# Unicorn_Light_Meter.net
KiCad netlist of a schematic drawn in EAGLE
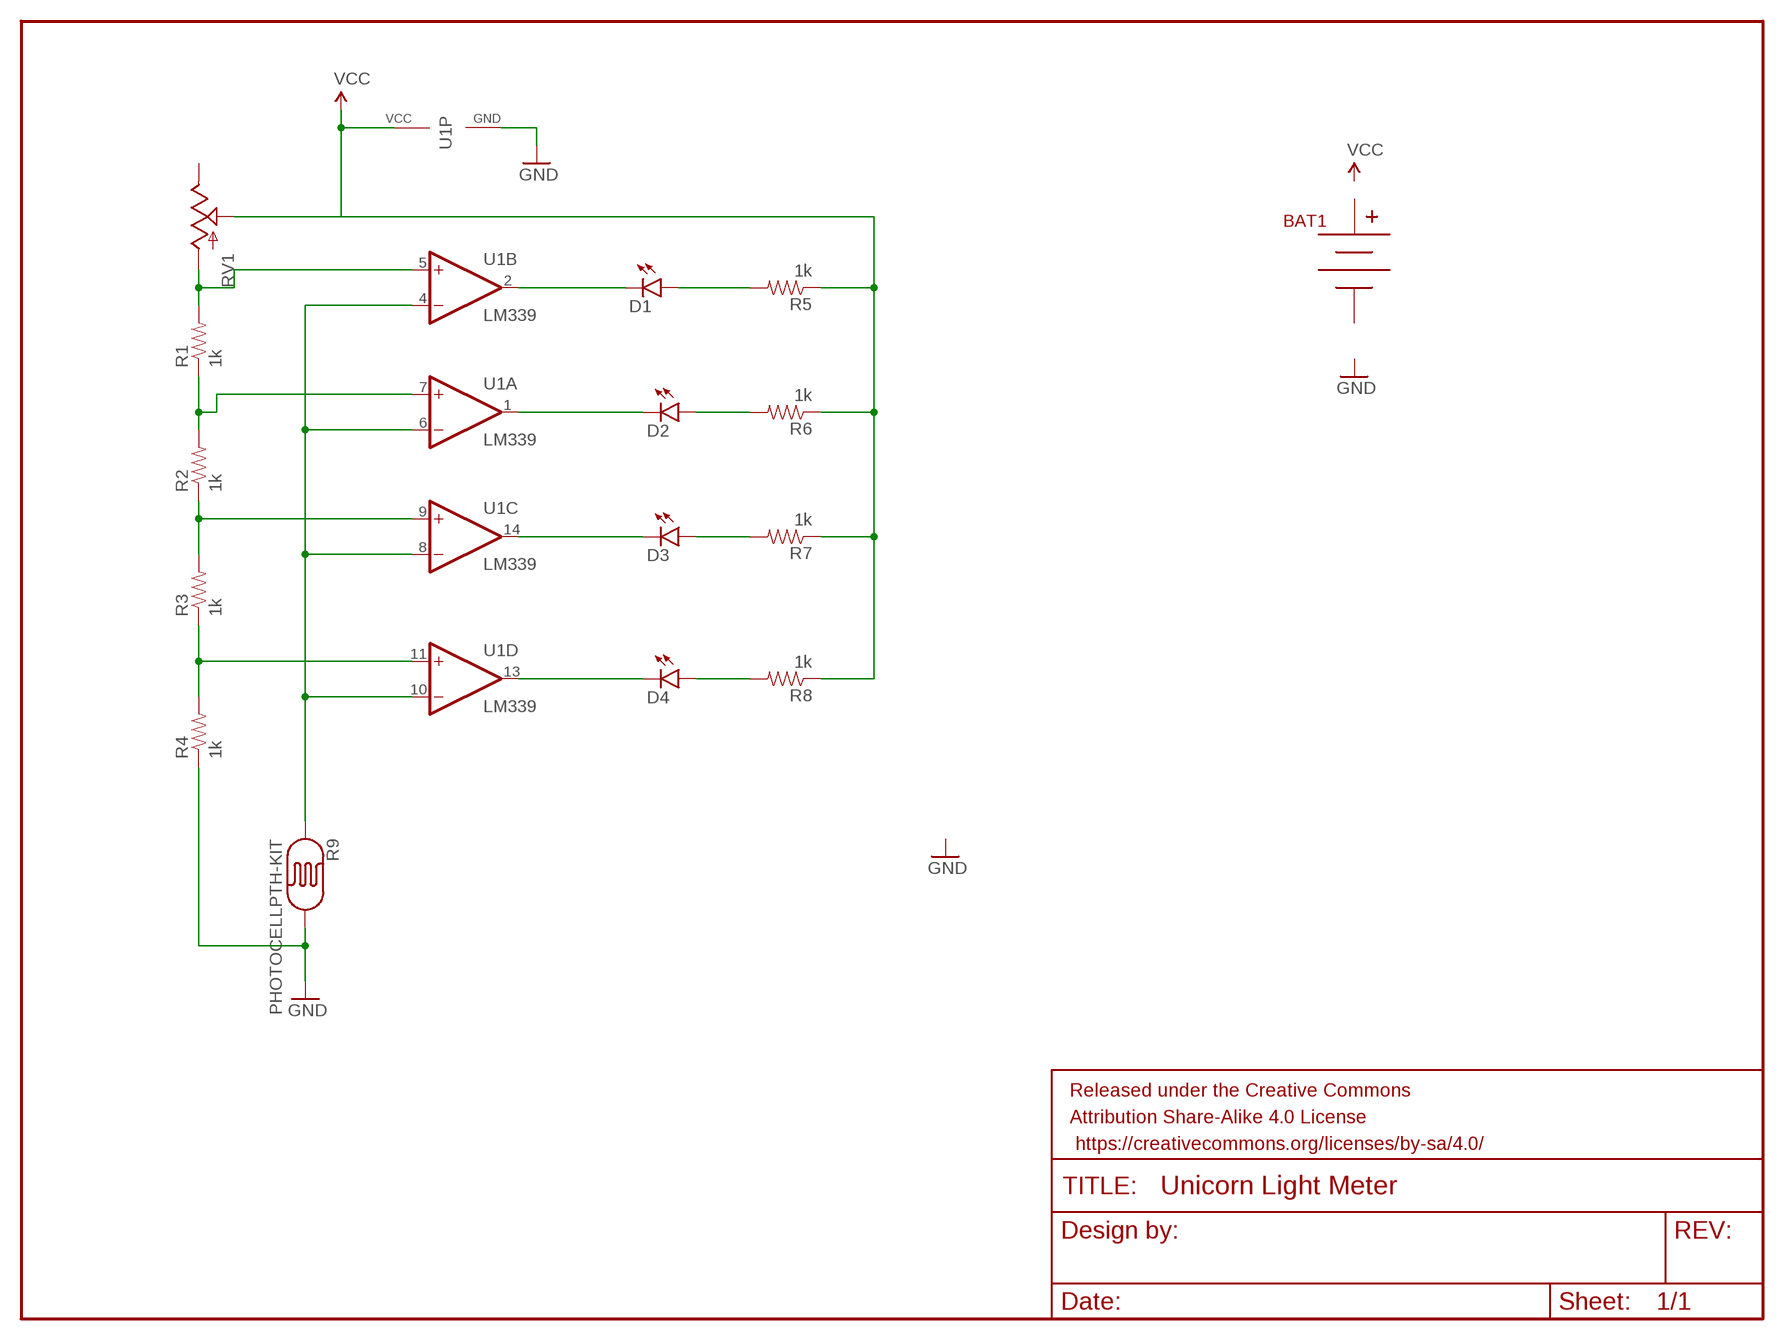
[diagram p0: schematic, sheet 1]

(export (version "E")
  (design (tool "Eeschema 10.0.6"))
  (components
    (comp (ref "BAT1")
      (value "BC9VPCKIT_SOLDERMASK")
      (footprint "eagle-import:BC9VPC_KIT")
      (libsource (lib "eagle-import") (part "BC9VPCKIT_SOLDERMASK"))
    )
    (comp (ref "D1")
      (value "LED5MM")
      (footprint "eagle-import:LED5MM")
      (libsource (lib "eagle-import") (part "LED5MM"))
    )
    (comp (ref "D2")
      (value "LED5MM")
      (footprint "eagle-import:LED5MM")
      (libsource (lib "eagle-import") (part "LED5MM"))
    )
    (comp (ref "D3")
      (value "LED5MM")
      (footprint "eagle-import:LED5MM")
      (libsource (lib "eagle-import") (part "LED5MM"))
    )
    (comp (ref "D4")
      (value "LED5MM")
      (footprint "eagle-import:LED5MM")
      (libsource (lib "eagle-import") (part "LED5MM"))
    )
    (comp (ref "FRAME1")
      (value "FRAME-LETTER")
      (footprint "eagle-import:CREATIVE_COMMONS")
      (libsource (lib "eagle-import") (part "FRAME-LETTER"))
    )
    (comp (ref "R1")
      (value "1k")
      (footprint "eagle-import:AXIAL-0.3EZ")
      (libsource (lib "eagle-import") (part "1KOHM-1/4W-5%(PTH)HORIZ-KIT"))
    )
    (comp (ref "R2")
      (value "1k")
      (footprint "eagle-import:AXIAL-0.3EZ")
      (libsource (lib "eagle-import") (part "1KOHM-1/4W-5%(PTH)HORIZ-KIT"))
    )
    (comp (ref "R3")
      (value "1k")
      (footprint "eagle-import:AXIAL-0.3EZ")
      (libsource (lib "eagle-import") (part "1KOHM-1/4W-5%(PTH)HORIZ-KIT"))
    )
    (comp (ref "R4")
      (value "1k")
      (footprint "eagle-import:AXIAL-0.3EZ")
      (libsource (lib "eagle-import") (part "1KOHM-1/4W-5%(PTH)HORIZ-KIT"))
    )
    (comp (ref "R5")
      (value "1k")
      (footprint "eagle-import:AXIAL-0.3EZ")
      (libsource (lib "eagle-import") (part "1KOHM-1/4W-5%(PTH)HORIZ-KIT"))
    )
    (comp (ref "R6")
      (value "1k")
      (footprint "eagle-import:AXIAL-0.3EZ")
      (libsource (lib "eagle-import") (part "1KOHM-1/4W-5%(PTH)HORIZ-KIT"))
    )
    (comp (ref "R7")
      (value "1k")
      (footprint "eagle-import:AXIAL-0.3EZ")
      (libsource (lib "eagle-import") (part "1KOHM-1/4W-5%(PTH)HORIZ-KIT"))
    )
    (comp (ref "R8")
      (value "1k")
      (footprint "eagle-import:AXIAL-0.3EZ")
      (libsource (lib "eagle-import") (part "1KOHM-1/4W-5%(PTH)HORIZ-KIT"))
    )
    (comp (ref "R9")
      (value "PHOTOCELLPTH-KIT")
      (footprint "eagle-import:PHOTOCELL-KIT")
      (libsource (lib "eagle-import") (part "PHOTOCELLPTH-KIT"))
    )
    (comp (ref "RV1")
      (value "POT100K_3362U")
      (footprint "eagle-import:3362U")
      (libsource (lib "eagle-import") (part "POT100K_3362U"))
    )
    (comp (ref "U1")
      (value "LM339")
      (footprint "eagle-import:TSSOP-14")
      (fields (field (name "PARTNUM") "LM339PWR"))
      (libsource (lib "eagle-import") (part "LM339"))
    )
  )
  (nets
    (net (code "1") (name "GND") (class "Default")
      (node (ref "R4") (pin "P$1") (pinfunction "1_P$1") (pintype "passive"))
      (node (ref "R9") (pin "2") (pinfunction "P$2_2") (pintype "bidirectional"))
      (node (ref "U1") (pin "12") (pinfunction "GND_12") (pintype "power_in"))
    )
    (net (code "2") (name "Net-(D1-C)") (class "Default")
      (node (ref "D1") (pin "K") (pinfunction "C_K") (pintype "passive"))
      (node (ref "U1") (pin "2") (pinfunction "OUT_2") (pintype "output"))
    )
    (net (code "3") (name "Net-(D2-C)") (class "Default")
      (node (ref "D2") (pin "K") (pinfunction "C_K") (pintype "passive"))
      (node (ref "U1") (pin "1") (pinfunction "OUT_1") (pintype "output"))
    )
    (net (code "4") (name "Net-(D3-C)") (class "Default")
      (node (ref "D3") (pin "K") (pinfunction "C_K") (pintype "passive"))
      (node (ref "U1") (pin "14") (pinfunction "OUT_14") (pintype "output"))
    )
    (net (code "5") (name "Net-(D4-C)") (class "Default")
      (node (ref "D4") (pin "K") (pinfunction "C_K") (pintype "passive"))
      (node (ref "U1") (pin "13") (pinfunction "OUT_13") (pintype "output"))
    )
    (net (code "6") (name "Net-(R1-1)") (class "Default")
      (node (ref "R1") (pin "P$1") (pinfunction "1_P$1") (pintype "passive"))
      (node (ref "R2") (pin "P$2") (pinfunction "2_P$2") (pintype "passive"))
      (node (ref "U1") (pin "7") (pinfunction "+IN_7") (pintype "input"))
    )
    (net (code "7") (name "Net-(R1-2)") (class "Default")
      (node (ref "R1") (pin "P$2") (pinfunction "2_P$2") (pintype "passive"))
      (node (ref "RV1") (pin "P$3") (pinfunction "A_P$3") (pintype "passive"))
      (node (ref "U1") (pin "5") (pinfunction "+IN_5") (pintype "input"))
    )
    (net (code "8") (name "Net-(R2-1)") (class "Default")
      (node (ref "R2") (pin "P$1") (pinfunction "1_P$1") (pintype "passive"))
      (node (ref "R3") (pin "P$2") (pinfunction "2_P$2") (pintype "passive"))
      (node (ref "U1") (pin "9") (pinfunction "+IN_9") (pintype "input"))
    )
    (net (code "9") (name "Net-(R3-1)") (class "Default")
      (node (ref "R3") (pin "P$1") (pinfunction "1_P$1") (pintype "passive"))
      (node (ref "R4") (pin "P$2") (pinfunction "2_P$2") (pintype "passive"))
      (node (ref "U1") (pin "11") (pinfunction "+IN_11") (pintype "input"))
    )
    (net (code "10") (name "Net-(R5-2)") (class "Default")
      (node (ref "D1") (pin "A") (pinfunction "A_A") (pintype "passive"))
      (node (ref "R5") (pin "P$2") (pinfunction "2_P$2") (pintype "passive"))
    )
    (net (code "11") (name "Net-(R6-2)") (class "Default")
      (node (ref "D2") (pin "A") (pinfunction "A_A") (pintype "passive"))
      (node (ref "R6") (pin "P$2") (pinfunction "2_P$2") (pintype "passive"))
    )
    (net (code "12") (name "Net-(R7-2)") (class "Default")
      (node (ref "D3") (pin "A") (pinfunction "A_A") (pintype "passive"))
      (node (ref "R7") (pin "P$2") (pinfunction "2_P$2") (pintype "passive"))
    )
    (net (code "13") (name "Net-(R8-2)") (class "Default")
      (node (ref "D4") (pin "A") (pinfunction "A_A") (pintype "passive"))
      (node (ref "R8") (pin "P$2") (pinfunction "2_P$2") (pintype "passive"))
    )
    (net (code "14") (name "Net-(R9-P$1)") (class "Default")
      (node (ref "R9") (pin "1") (pinfunction "P$1_1") (pintype "bidirectional"))
      (node (ref "U1") (pin "10") (pinfunction "-IN_10") (pintype "input"))
      (node (ref "U1") (pin "4") (pinfunction "-IN_4") (pintype "input"))
      (node (ref "U1") (pin "6") (pinfunction "-IN_6") (pintype "input"))
      (node (ref "U1") (pin "8") (pinfunction "-IN_8") (pintype "input"))
    )
    (net (code "15") (name "VCC") (class "Default")
      (node (ref "R5") (pin "P$1") (pinfunction "1_P$1") (pintype "passive"))
      (node (ref "R6") (pin "P$1") (pinfunction "1_P$1") (pintype "passive"))
      (node (ref "R7") (pin "P$1") (pinfunction "1_P$1") (pintype "passive"))
      (node (ref "R8") (pin "P$1") (pinfunction "1_P$1") (pintype "passive"))
      (node (ref "RV1") (pin "P$2") (pinfunction "S_P$2") (pintype "passive"))
      (node (ref "U1") (pin "3") (pinfunction "VCC_3") (pintype "power_in"))
    )
    (net (code "16") (name "unconnected-(BAT1-PadV+)") (class "Default")
      (node (ref "BAT1") (pin "V+") (pinfunction "V+_V+") (pintype "bidirectional"))
    )
    (net (code "17") (name "unconnected-(BAT1-PadV-)") (class "Default")
      (node (ref "BAT1") (pin "V-") (pinfunction "V-_V-") (pintype "bidirectional"))
    )
    (net (code "18") (name "unconnected-(RV1-E-PadP$1)") (class "Default")
      (node (ref "RV1") (pin "P$1") (pinfunction "E_P$1") (pintype "passive"))
    )
  )
)
